# SWITCH.net
KiCad netlist of a schematic drawn in Altium Designer
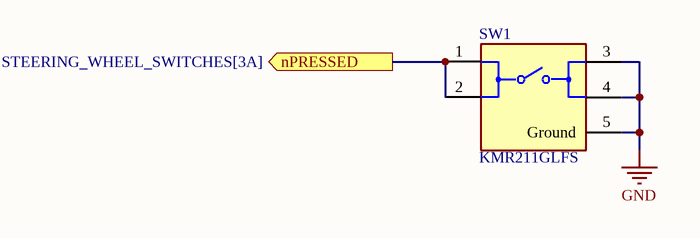
[diagram p0: SWITCH.SchDoc]

(export (version "E")
  (design (tool "Eeschema 10.0.6"))
  (components
    (comp (ref "SW1")
      (value "KMR211GLFS")
      (footprint "FP-KMR211GLFS-MFG")
      (description "SWITCH TACTILE SPST-NO 0.05A 32V")
      (libsource (lib "Altium Content Vault") (part "99988cc0f9d3d39bd794ae22da860e5"))
    )
  )
  (nets
    (net (code "1") (name "/nPRESSED") (class "Default")
      (node (ref "SW1") (pin "1") (pinfunction "1_1") (pintype "passive"))
      (node (ref "SW1") (pin "2") (pinfunction "2_2") (pintype "passive"))
    )
    (net (code "2") (name "GND") (class "Default")
      (node (ref "SW1") (pin "3") (pinfunction "3_3") (pintype "passive"))
      (node (ref "SW1") (pin "4") (pinfunction "4_4") (pintype "passive"))
      (node (ref "SW1") (pin "5") (pinfunction "Ground_5") (pintype "power_in"))
    )
  )
)
